# 2_0.net
KiCad netlist of a schematic drawn in Altium Designer
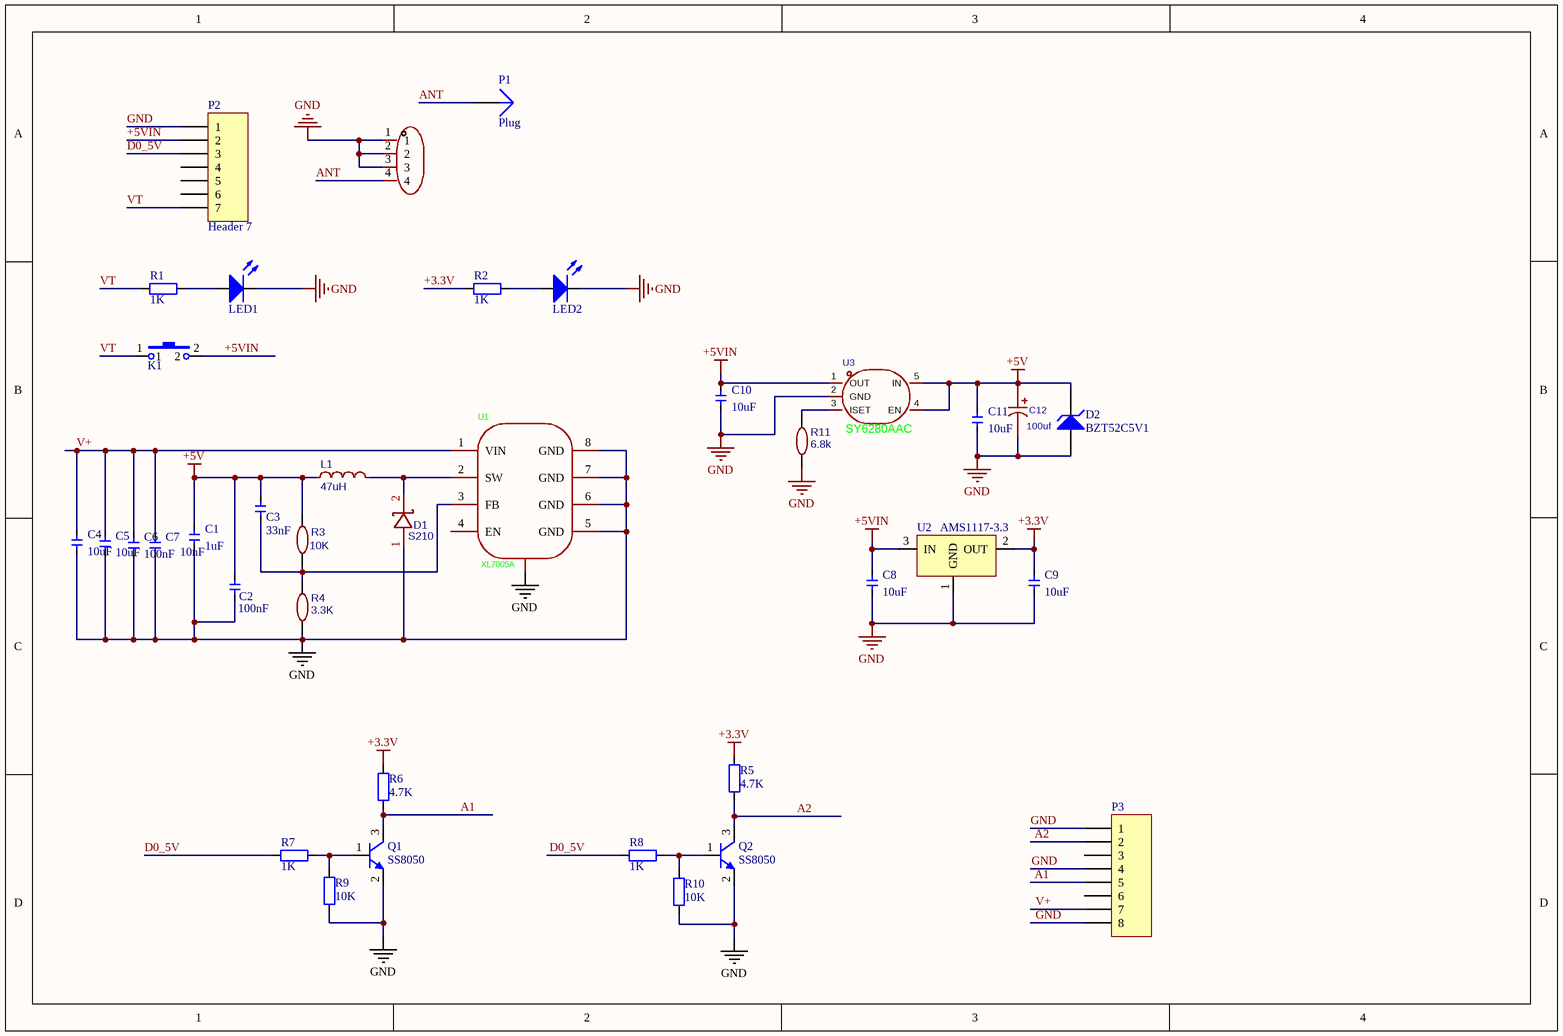
[diagram p0: 遥控2.0.SchDoc]

(export (version "E")
  (design (tool "Eeschema 10.0.6"))
  (components
    (comp (ref "C1")
      (value "1uF")
      (footprint "CAP-0603")
      (description "无极性电容")
      (fields (field (name "PUBLISHER") "Altium Limited"))
      (libsource (lib "Arrowy_Racing") (part "Cap"))
    )
    (comp (ref "C2")
      (value "100nF")
      (footprint "CAP-0603")
      (description "无极性电容")
      (fields (field (name "PUBLISHER") "Altium Limited"))
      (libsource (lib "Arrowy_Racing") (part "Cap"))
    )
    (comp (ref "C3")
      (value "33nF")
      (footprint "CAP-0603")
      (description "无极性电容")
      (fields (field (name "PUBLISHER") "Altium Limited"))
      (libsource (lib "Arrowy_Racing") (part "Cap"))
    )
    (comp (ref "C4")
      (value "10uF")
      (footprint "0805")
      (description "无极性电容")
      (fields (field (name "PUBLISHER") "Altium Limited"))
      (libsource (lib "Arrowy_Racing") (part "Cap"))
    )
    (comp (ref "C5")
      (value "10uF")
      (footprint "0805")
      (description "无极性电容")
      (fields (field (name "PUBLISHER") "Altium Limited"))
      (libsource (lib "Arrowy_Racing") (part "Cap"))
    )
    (comp (ref "C6")
      (value "100nF")
      (footprint "0805")
      (description "无极性电容")
      (fields (field (name "PUBLISHER") "Altium Limited"))
      (libsource (lib "Arrowy_Racing") (part "Cap"))
    )
    (comp (ref "C7")
      (value "10nF")
      (footprint "0805")
      (description "无极性电容")
      (fields (field (name "PUBLISHER") "Altium Limited"))
      (libsource (lib "Arrowy_Racing") (part "Cap"))
    )
    (comp (ref "C8")
      (value "10uF")
      (footprint "CAP-0603")
      (description "无极性电容")
      (fields (field (name "PUBLISHER") "Altium Limited"))
      (libsource (lib "Arrowy_Racing") (part "Cap"))
    )
    (comp (ref "C9")
      (value "10uF")
      (footprint "CAP-0603")
      (description "无极性电容")
      (fields (field (name "PUBLISHER") "Altium Limited"))
      (libsource (lib "Arrowy_Racing") (part "Cap"))
    )
    (comp (ref "C10")
      (value "10uF")
      (footprint "CAP-0603")
      (description "无极性电容")
      (fields (field (name "PUBLISHER") "Altium Limited"))
      (libsource (lib "Arrowy_Racing") (part "Cap"))
    )
    (comp (ref "C11")
      (value "10uF")
      (footprint "CAP-0603")
      (description "无极性电容")
      (fields (field (name "PUBLISHER") "Altium Limited"))
      (libsource (lib "Arrowy_Racing") (part "Cap"))
    )
    (comp (ref "C12")
      (value "TAJB107M010RNJ")
      (footprint "CASE-B_3528")
      (description "100uF")
      (fields (field (name "SYMBOL") "100uf"))
      (libsource (lib "altium-import") (part "root_3_JVJ10V100M5X5_"))
    )
    (comp (ref "D1")
      (value "S210")
      (footprint "SOD-123")
      (fields (field (name "MANUFACTURER PART") "B340A") (field (name "MANUFACTURER") "MDD"))
      (libsource (lib "altium-import") (part "root_3_B340A_"))
    )
    (comp (ref "D2")
      (value "BZT52C5V1")
      (footprint "SOD-123")
      (description "Zener Diode")
      (fields (field (name "PUBLISHER") "Altium Limited"))
      (libsource (lib "Miscellaneous Devices") (part "D Zener"))
    )
    (comp (ref "K1")
      (value "SW-PB")
      (footprint "SW-SMD_4P-L6.0-W6.0")
      (description "微动开关")
      (fields (field (name "SUPPLITER PART") "C961737") (field (name "PUBLISHER") "Altium Limited"))
      (libsource (lib "Arrowy_Racing") (part "SW-PB"))
    )
    (comp (ref "L1")
      (value "47uH")
      (footprint "IND-SMD_L4.0-W4.0_FNR4012S")
      (fields (field (name "MANUFACTURER") "SXN") (field (name "MANUFACTURER PART") "SMDRI127-680MT"))
      (libsource (lib "altium-import") (part "root_0_68uH_"))
    )
    (comp (ref "LED1")
      (value "LED")
      (footprint "LED_0805")
      (description "发光二极管")
      (fields (field (name "PUBLISHER") "Altium Limited"))
      (libsource (lib "Arrowy_Racing") (part "LED"))
    )
    (comp (ref "LED2")
      (value "LED")
      (footprint "LED_0805")
      (description "发光二极管")
      (fields (field (name "PUBLISHER") "Altium Limited"))
      (libsource (lib "Arrowy_Racing") (part "LED"))
    )
    (comp (ref "P1")
      (value "Plug")
      (footprint "HEADER_1")
      (description "安装孔")
      (fields (field (name "PUBLISHER") "Altium Limited"))
      (libsource (lib "Arrowy_Racing") (part "Plug"))
    )
    (comp (ref "P2")
      (value "Header 7")
      (footprint "HDR1X7")
      (description "Header, 7-Pin")
      (fields (field (name "PUBLISHER") "Altium Limited"))
      (libsource (lib "Miscellaneous Connectors") (part "Header 7"))
    )
    (comp (ref "P3")
      (value "Header 8")
      (footprint "XH2.54-W-8P")
      (description "Header, 8-Pin")
      (fields (field (name "PUBLISHER") "Altium Limited"))
      (libsource (lib "Miscellaneous Connectors") (part "Header 8"))
    )
    (comp (ref "Q1")
      (value "SS8050")
      (footprint "SOT-23")
      (description "NPN贴片三极管")
      (fields (field (name "PUBLISHER") "Altium Limited"))
      (libsource (lib "Arrowy_Racing") (part "SS8050"))
    )
    (comp (ref "Q2")
      (value "SS8050")
      (footprint "SOT-23")
      (description "NPN贴片三极管")
      (fields (field (name "PUBLISHER") "Altium Limited"))
      (libsource (lib "Arrowy_Racing") (part "SS8050"))
    )
    (comp (ref "R1")
      (value "1K")
      (footprint "0603 - duplicate1")
      (description "贴片电阻")
      (fields (field (name "PUBLISHER") "Altium Limited"))
      (libsource (lib "") (part "Res_3"))
    )
    (comp (ref "R2")
      (value "1K")
      (footprint "0603 - duplicate1")
      (description "贴片电阻")
      (fields (field (name "PUBLISHER") "Altium Limited"))
      (libsource (lib "") (part "Res_3"))
    )
    (comp (ref "R3")
      (value "10K")
      (footprint "0603 - duplicate1")
      (fields (field (name "MANUFACTURER") "UniOhm") (field (name "MANUFACTURER PART") "0603WAF1001T5E"))
      (libsource (lib "altium-import") (part "root_1_1K_"))
    )
    (comp (ref "R4")
      (value "3.3K")
      (footprint "0603 - duplicate1")
      (fields (field (name "MANUFACTURER") "UniOhm") (field (name "MANUFACTURER PART") "0603WAF3001T5E"))
      (libsource (lib "altium-import") (part "root_3_3K_"))
    )
    (comp (ref "R5")
      (value "4.7K")
      (footprint "0603 - duplicate1")
      (description "贴片电阻")
      (fields (field (name "PUBLISHER") "Altium Limited"))
      (libsource (lib "") (part "Res_1"))
    )
    (comp (ref "R6")
      (value "4.7K")
      (footprint "0603 - duplicate1")
      (description "贴片电阻")
      (fields (field (name "PUBLISHER") "Altium Limited"))
      (libsource (lib "") (part "Res_1"))
    )
    (comp (ref "R7")
      (value "1K")
      (footprint "0603 - duplicate1")
      (description "贴片电阻")
      (fields (field (name "PUBLISHER") "Altium Limited"))
      (libsource (lib "") (part "Res_2"))
    )
    (comp (ref "R8")
      (value "1K")
      (footprint "0603 - duplicate1")
      (description "贴片电阻")
      (fields (field (name "PUBLISHER") "Altium Limited"))
      (libsource (lib "") (part "Res_2"))
    )
    (comp (ref "R9")
      (value "10K")
      (footprint "0603 - duplicate1")
      (description "贴片电阻")
      (fields (field (name "PUBLISHER") "Altium Limited"))
      (libsource (lib "Arrowy_Racing") (part "Res"))
    )
    (comp (ref "R10")
      (value "10K")
      (footprint "0603 - duplicate1")
      (description "贴片电阻")
      (fields (field (name "PUBLISHER") "Altium Limited"))
      (libsource (lib "Arrowy_Racing") (part "Res"))
    )
    (comp (ref "R11")
      (value "6.8k")
      (footprint "0603 - duplicate1")
      (fields (field (name "MANUFACTURER") "UniOhm") (field (name "MANUFACTURER PART") "0603WAF3001T5E"))
      (libsource (lib "altium-import") (part "root_3_3K_"))
    )
    (comp (ref "RF1")
      (value "6GHz")
      (footprint "CONN-SMD_GT-RF1125A-01G")
      (fields
        (field (name "MANUFACTURER") "G-Switch(品赞)")
        (field (name "MANUFACTURER PART") "GT-RF1125A-01G")
      )
      (libsource (lib "altium-import") (part "root_0_GT-RF1125A-01G_"))
    )
    (comp (ref "U1")
      (value "XL7005A")
      (footprint "SOIC-8_L4.9-W3.9-P1.27-LS6.0-BL-EP3.1-1")
      (fields (field (name "MANUFACTURER") "XLSEMI(芯龙)"))
      (libsource (lib "altium-import") (part "root_0_XL7005A_"))
    )
    (comp (ref "U2")
      (value "AMS1117-3.3")
      (footprint "SOT89")
      (description "3.3V稳压芯片")
      (libsource (lib "Arrowy_Racing") (part "AMS1117"))
    )
    (comp (ref "U3")
      (value "SY6280AAC")
      (footprint "SOT-23-5")
      (libsource (lib "altium-import") (part "root_3_SY6280AAC_"))
    )
  )
  (nets
    (net (code "1") (name "+3.3V") (class "Default")
      (node (ref "C9") (pin "2") (pinfunction "2_2") (pintype "passive"))
      (node (ref "R2") (pin "2") (pinfunction "2_2") (pintype "passive"))
      (node (ref "R5") (pin "1") (pinfunction "1_1") (pintype "passive"))
      (node (ref "R6") (pin "1") (pinfunction "1_1") (pintype "passive"))
      (node (ref "U2") (pin "2") (pinfunction "OUT_2") (pintype "passive"))
    )
    (net (code "2") (name "+5V") (class "Default")
      (node (ref "C1") (pin "2") (pinfunction "2_2") (pintype "passive"))
      (node (ref "C11") (pin "2") (pinfunction "2_2") (pintype "passive"))
      (node (ref "C12") (pin "1") (pinfunction "1_1") (pintype "passive"))
      (node (ref "C2") (pin "2") (pinfunction "2_2") (pintype "passive"))
      (node (ref "C3") (pin "2") (pinfunction "2_2") (pintype "passive"))
      (node (ref "D2") (pin "2") (pinfunction "K_2") (pintype "passive"))
      (node (ref "L1") (pin "1") (pinfunction "1_1") (pintype "passive"))
      (node (ref "R3") (pin "2") (pinfunction "2_2") (pintype "passive"))
      (node (ref "U3") (pin "4") (pinfunction "EN_4") (pintype "passive"))
      (node (ref "U3") (pin "5") (pinfunction "IN_5") (pintype "passive"))
    )
    (net (code "3") (name "+5VIN") (class "Default")
      (node (ref "C10") (pin "2") (pinfunction "2_2") (pintype "passive"))
      (node (ref "C8") (pin "2") (pinfunction "2_2") (pintype "passive"))
      (node (ref "K1") (pin "2") (pinfunction "2_2") (pintype "passive"))
      (node (ref "P2") (pin "2") (pinfunction "2_2") (pintype "passive"))
      (node (ref "U2") (pin "3") (pinfunction "IN_3") (pintype "passive"))
      (node (ref "U3") (pin "1") (pinfunction "OUT_1") (pintype "passive"))
    )
    (net (code "4") (name "/A1") (class "Default")
      (node (ref "P3") (pin "5") (pinfunction "5_5") (pintype "passive"))
      (node (ref "Q1") (pin "3") (pinfunction "C_3") (pintype "passive"))
      (node (ref "R6") (pin "2") (pinfunction "2_2") (pintype "passive"))
    )
    (net (code "5") (name "/A2") (class "Default")
      (node (ref "P3") (pin "2") (pinfunction "2_2") (pintype "passive"))
      (node (ref "Q2") (pin "3") (pinfunction "C_3") (pintype "passive"))
      (node (ref "R5") (pin "2") (pinfunction "2_2") (pintype "passive"))
    )
    (net (code "6") (name "/ANT") (class "Default")
      (node (ref "P1") (pin "1") (pinfunction "1_1") (pintype "passive"))
      (node (ref "RF1") (pin "4") (pinfunction "4_4") (pintype "passive"))
    )
    (net (code "7") (name "/D0_5V") (class "Default")
      (node (ref "P2") (pin "3") (pinfunction "3_3") (pintype "passive"))
      (node (ref "R7") (pin "1") (pinfunction "1_1") (pintype "passive"))
      (node (ref "R8") (pin "1") (pinfunction "1_1") (pintype "passive"))
    )
    (net (code "8") (name "/V+") (class "Default")
      (node (ref "C4") (pin "2") (pinfunction "2_2") (pintype "passive"))
      (node (ref "C5") (pin "2") (pinfunction "2_2") (pintype "passive"))
      (node (ref "C6") (pin "2") (pinfunction "2_2") (pintype "passive"))
      (node (ref "C7") (pin "2") (pinfunction "2_2") (pintype "passive"))
      (node (ref "P3") (pin "7") (pinfunction "7_7") (pintype "passive"))
      (node (ref "U1") (pin "1") (pinfunction "VIN_1") (pintype "passive"))
    )
    (net (code "9") (name "/VT") (class "Default")
      (node (ref "K1") (pin "1") (pinfunction "1_1") (pintype "passive"))
      (node (ref "P2") (pin "7") (pinfunction "7_7") (pintype "passive"))
      (node (ref "R1") (pin "2") (pinfunction "2_2") (pintype "passive"))
    )
    (net (code "10") (name "GND") (class "Default")
      (node (ref "C1") (pin "1") (pinfunction "1_1") (pintype "passive"))
      (node (ref "C10") (pin "1") (pinfunction "1_1") (pintype "passive"))
      (node (ref "C11") (pin "1") (pinfunction "1_1") (pintype "passive"))
      (node (ref "C12") (pin "2") (pinfunction "2_2") (pintype "passive"))
      (node (ref "C2") (pin "1") (pinfunction "1_1") (pintype "passive"))
      (node (ref "C4") (pin "1") (pinfunction "1_1") (pintype "passive"))
      (node (ref "C5") (pin "1") (pinfunction "1_1") (pintype "passive"))
      (node (ref "C6") (pin "1") (pinfunction "1_1") (pintype "passive"))
      (node (ref "C7") (pin "1") (pinfunction "1_1") (pintype "passive"))
      (node (ref "C8") (pin "1") (pinfunction "1_1") (pintype "passive"))
      (node (ref "C9") (pin "1") (pinfunction "1_1") (pintype "passive"))
      (node (ref "D1") (pin "1") (pinfunction "A_1") (pintype "passive"))
      (node (ref "D2") (pin "1") (pinfunction "A_1") (pintype "passive"))
      (node (ref "LED1") (pin "2") (pinfunction "K_2") (pintype "passive"))
      (node (ref "LED2") (pin "2") (pinfunction "K_2") (pintype "passive"))
      (node (ref "P2") (pin "1") (pinfunction "1_1") (pintype "passive"))
      (node (ref "P3") (pin "1") (pinfunction "1_1") (pintype "passive"))
      (node (ref "P3") (pin "4") (pinfunction "4_4") (pintype "passive"))
      (node (ref "P3") (pin "8") (pinfunction "8_8") (pintype "passive"))
      (node (ref "Q1") (pin "2") (pinfunction "E_2") (pintype "passive"))
      (node (ref "Q2") (pin "2") (pinfunction "E_2") (pintype "passive"))
      (node (ref "R10") (pin "1") (pinfunction "1_1") (pintype "passive"))
      (node (ref "R11") (pin "2") (pinfunction "2_2") (pintype "passive"))
      (node (ref "R4") (pin "2") (pinfunction "2_2") (pintype "passive"))
      (node (ref "R9") (pin "1") (pinfunction "1_1") (pintype "passive"))
      (node (ref "RF1") (pin "1") (pinfunction "1_1") (pintype "passive"))
      (node (ref "RF1") (pin "2") (pinfunction "2_2") (pintype "passive"))
      (node (ref "RF1") (pin "3") (pinfunction "3_3") (pintype "passive"))
      (node (ref "U1") (pin "5") (pinfunction "GND_5") (pintype "passive"))
      (node (ref "U1") (pin "6") (pinfunction "GND_6") (pintype "passive"))
      (node (ref "U1") (pin "7") (pinfunction "GND_7") (pintype "passive"))
      (node (ref "U1") (pin "8") (pinfunction "GND_8") (pintype "passive"))
      (node (ref "U1") (pin "9") (pinfunction "9_9") (pintype "passive"))
      (node (ref "U2") (pin "1") (pinfunction "GND_1") (pintype "passive"))
      (node (ref "U3") (pin "2") (pinfunction "GND_2") (pintype "passive"))
    )
    (net (code "11") (name "Net-(D1-K)") (class "Default")
      (node (ref "D1") (pin "2") (pinfunction "K_2") (pintype "passive"))
      (node (ref "L1") (pin "2") (pinfunction "2_2") (pintype "passive"))
      (node (ref "U1") (pin "2") (pinfunction "SW_2") (pintype "passive"))
    )
    (net (code "12") (name "Net-(LED1-A)") (class "Default")
      (node (ref "LED1") (pin "1") (pinfunction "A_1") (pintype "passive"))
      (node (ref "R1") (pin "1") (pinfunction "1_1") (pintype "passive"))
    )
    (net (code "13") (name "Net-(LED2-A)") (class "Default")
      (node (ref "LED2") (pin "1") (pinfunction "A_1") (pintype "passive"))
      (node (ref "R2") (pin "1") (pinfunction "1_1") (pintype "passive"))
    )
    (net (code "14") (name "Net-(Q1-B)") (class "Default")
      (node (ref "Q1") (pin "1") (pinfunction "B_1") (pintype "passive"))
      (node (ref "R7") (pin "2") (pinfunction "2_2") (pintype "passive"))
      (node (ref "R9") (pin "2") (pinfunction "2_2") (pintype "passive"))
    )
    (net (code "15") (name "Net-(Q2-B)") (class "Default")
      (node (ref "Q2") (pin "1") (pinfunction "B_1") (pintype "passive"))
      (node (ref "R10") (pin "2") (pinfunction "2_2") (pintype "passive"))
      (node (ref "R8") (pin "2") (pinfunction "2_2") (pintype "passive"))
    )
    (net (code "16") (name "Net-(U1-FB)") (class "Default")
      (node (ref "C3") (pin "1") (pinfunction "1_1") (pintype "passive"))
      (node (ref "R3") (pin "1") (pinfunction "1_1") (pintype "passive"))
      (node (ref "R4") (pin "1") (pinfunction "1_1") (pintype "passive"))
      (node (ref "U1") (pin "3") (pinfunction "FB_3") (pintype "passive"))
    )
    (net (code "17") (name "Net-(U3-ISET)") (class "Default")
      (node (ref "R11") (pin "1") (pinfunction "1_1") (pintype "passive"))
      (node (ref "U3") (pin "3") (pinfunction "ISET_3") (pintype "passive"))
    )
    (net (code "18") (name "unconnected-(P2-Pad4)") (class "Default")
      (node (ref "P2") (pin "4") (pinfunction "4_4") (pintype "passive"))
    )
    (net (code "19") (name "unconnected-(P2-Pad5)") (class "Default")
      (node (ref "P2") (pin "5") (pinfunction "5_5") (pintype "passive"))
    )
    (net (code "20") (name "unconnected-(P2-Pad6)") (class "Default")
      (node (ref "P2") (pin "6") (pinfunction "6_6") (pintype "passive"))
    )
    (net (code "21") (name "unconnected-(P3-Pad3)") (class "Default")
      (node (ref "P3") (pin "3") (pinfunction "3_3") (pintype "passive"))
    )
    (net (code "22") (name "unconnected-(P3-Pad6)") (class "Default")
      (node (ref "P3") (pin "6") (pinfunction "6_6") (pintype "passive"))
    )
    (net (code "23") (name "unconnected-(U1-EN-Pad4)") (class "Default")
      (node (ref "U1") (pin "4") (pinfunction "EN_4") (pintype "passive"))
    )
  )
)
